# smart-plug.net
KiCad netlist of a schematic drawn in Altium Designer
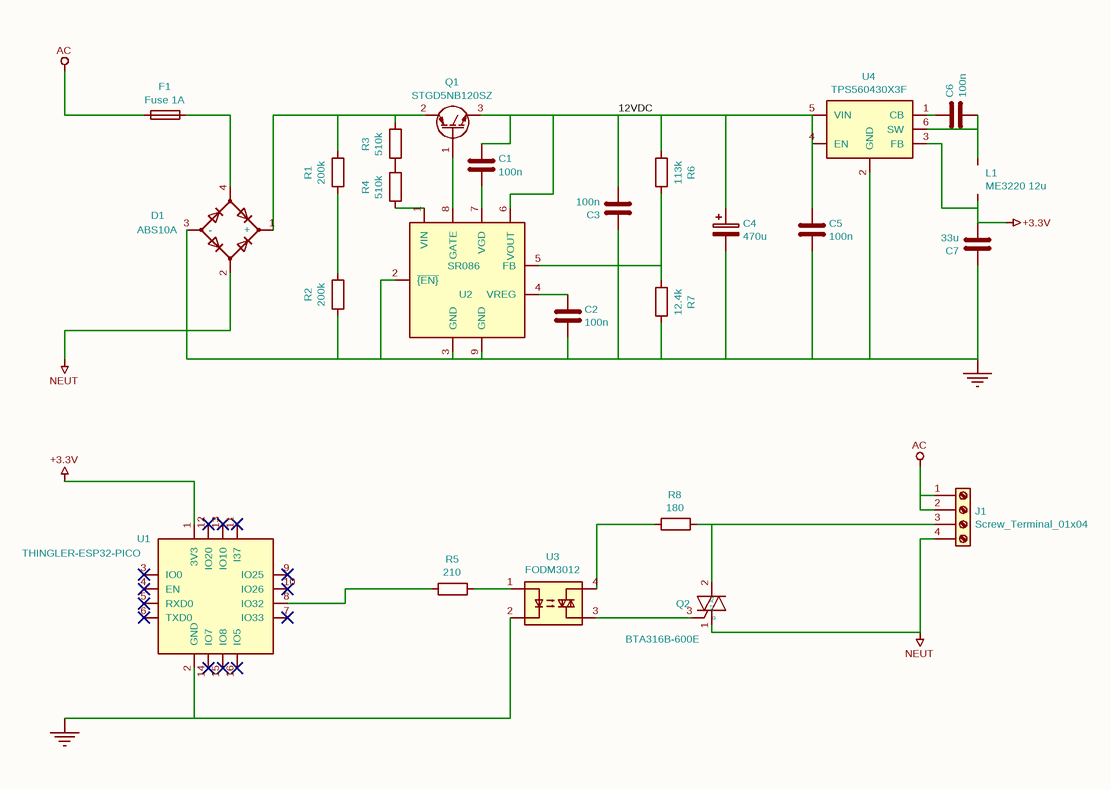
[diagram p0: smart-plug.SchDoc]

(export (version "E")
  (design (tool "Eeschema 10.0.6"))
  (components
    (comp (ref "C1") (value "100n") (libsource (lib "Device") (part "C")))
    (comp (ref "C2") (value "100n") (libsource (lib "Device") (part "C")))
    (comp (ref "C3") (value "100n") (libsource (lib "Device") (part "C")))
    (comp (ref "C4") (value "470u") (libsource (lib "Device") (part "C_Polarized")))
    (comp (ref "C5") (value "100n") (libsource (lib "Device") (part "C")))
    (comp (ref "C6") (value "100n") (libsource (lib "Device") (part "C")))
    (comp (ref "C7") (value "33u") (libsource (lib "Device") (part "C")))
    (comp (ref "D1") (value "ABS10A") (libsource (lib "Device") (part "D_Bridge_+A-A")))
    (comp (ref "F1") (value "Fuse 1A") (libsource (lib "Device") (part "Fuse")))
    (comp (ref "J1")
      (value "Screw_Terminal_01x04")
      (libsource (lib "Connector") (part "Screw_Terminal_01x04"))
    )
    (comp (ref "L1") (value "ME3220 12u") (libsource (lib "Device") (part "L")))
    (comp (ref "Q1") (value "STGD5NB120SZ") (libsource (lib "Device") (part "Q_NIGBT_GCE")))
    (comp (ref "Q2") (value "BTA316B-600E") (libsource (lib "Triac_Thyristor") (part "BT138-600")))
    (comp (ref "R1") (value "200k") (libsource (lib "Device") (part "R")))
    (comp (ref "R2") (value "200k") (libsource (lib "Device") (part "R")))
    (comp (ref "R3") (value "510k") (libsource (lib "Device") (part "R")))
    (comp (ref "R4") (value "510k") (libsource (lib "Device") (part "R")))
    (comp (ref "R5") (value "210") (libsource (lib "") (part "R_1")))
    (comp (ref "R6") (value "113k") (libsource (lib "") (part "R_2")))
    (comp (ref "R7") (value "12.4k") (libsource (lib "") (part "R_2")))
    (comp (ref "R8") (value "180") (libsource (lib "") (part "R_1")))
    (comp (ref "U1")
      (value "THINGLER-ESP32-PICO")
      (libsource (lib "smart-plug") (part "THINGLER-ESP32-PICO"))
    )
    (comp (ref "U2") (value "SR086") (libsource (lib "smart-plug") (part "SR086")))
    (comp (ref "U3") (value "FODM3012") (libsource (lib "Relay_SolidState") (part "FODM3012")))
    (comp (ref "U4") (value "TPS560430X3F") (libsource (lib "smart-plug") (part "TPS560430")))
  )
  (nets
    (net (code "1") (name "+3.3V") (class "Default")
      (node (ref "C7") (pin "2") (pinfunction "2_2") (pintype "passive"))
      (node (ref "L1") (pin "2") (pinfunction "2_2") (pintype "passive"))
      (node (ref "U1") (pin "1") (pinfunction "3V3_1") (pintype "passive"))
      (node (ref "U4") (pin "3") (pinfunction "FB_3") (pintype "passive"))
    )
    (net (code "2") (name "/12VDC") (class "Default")
      (node (ref "C1") (pin "1") (pinfunction "1_1") (pintype "passive"))
      (node (ref "C3") (pin "2") (pinfunction "2_2") (pintype "passive"))
      (node (ref "C4") (pin "1") (pinfunction "1_1") (pintype "passive"))
      (node (ref "C5") (pin "1") (pinfunction "1_1") (pintype "passive"))
      (node (ref "Q1") (pin "3") (pinfunction "E_3") (pintype "passive"))
      (node (ref "R6") (pin "2") (pinfunction "2_2") (pintype "passive"))
      (node (ref "U2") (pin "6") (pinfunction "VOUT_6") (pintype "passive"))
      (node (ref "U4") (pin "4") (pinfunction "EN_4") (pintype "passive"))
      (node (ref "U4") (pin "5") (pinfunction "VIN_5") (pintype "passive"))
    )
    (net (code "3") (name "AC") (class "Default")
      (node (ref "F1") (pin "2") (pinfunction "2_2") (pintype "passive"))
      (node (ref "J1") (pin "1") (pinfunction "Pin_1_1") (pintype "passive"))
      (node (ref "J1") (pin "2") (pinfunction "Pin_2_2") (pintype "passive"))
    )
    (net (code "4") (name "Earth") (class "Default")
      (node (ref "C2") (pin "2") (pinfunction "2_2") (pintype "passive"))
      (node (ref "C3") (pin "1") (pinfunction "1_1") (pintype "passive"))
      (node (ref "C4") (pin "2") (pinfunction "2_2") (pintype "passive"))
      (node (ref "C5") (pin "2") (pinfunction "2_2") (pintype "passive"))
      (node (ref "C7") (pin "1") (pinfunction "1_1") (pintype "passive"))
      (node (ref "D1") (pin "3") (pinfunction "-_3") (pintype "passive"))
      (node (ref "R2") (pin "2") (pinfunction "2_2") (pintype "passive"))
      (node (ref "R7") (pin "1") (pinfunction "1_1") (pintype "passive"))
      (node (ref "U1") (pin "2") (pinfunction "GND_2") (pintype "passive"))
      (node (ref "U2") (pin "2") (pinfunction "~{{EN}}_2") (pintype "passive"))
      (node (ref "U2") (pin "3") (pinfunction "GND_3") (pintype "passive"))
      (node (ref "U2") (pin "9") (pinfunction "GND_9") (pintype "passive"))
      (node (ref "U3") (pin "2") (pinfunction "2_2") (pintype "passive"))
      (node (ref "U4") (pin "2") (pinfunction "GND_2") (pintype "passive"))
    )
    (net (code "5") (name "NEUT") (class "Default")
      (node (ref "D1") (pin "2") (pinfunction "2_2") (pintype "passive"))
      (node (ref "J1") (pin "4") (pinfunction "Pin_4_4") (pintype "passive"))
      (node (ref "Q2") (pin "1") (pinfunction "A1_1") (pintype "passive"))
    )
    (net (code "6") (name "Net-(D1-+)") (class "Default")
      (node (ref "D1") (pin "1") (pinfunction "+_1") (pintype "passive"))
      (node (ref "Q1") (pin "2") (pinfunction "C_2") (pintype "passive"))
      (node (ref "R1") (pin "1") (pinfunction "1_1") (pintype "passive"))
      (node (ref "R3") (pin "1") (pinfunction "1_1") (pintype "passive"))
    )
    (net (code "7") (name "Net-(D1-Pad4)") (class "Default")
      (node (ref "D1") (pin "4") (pinfunction "4_4") (pintype "passive"))
      (node (ref "F1") (pin "1") (pinfunction "1_1") (pintype "passive"))
    )
    (net (code "8") (name "Net-(J1-Pin_3)") (class "Default")
      (node (ref "J1") (pin "3") (pinfunction "Pin_3_3") (pintype "passive"))
      (node (ref "Q2") (pin "2") (pinfunction "A2_2") (pintype "passive"))
      (node (ref "R8") (pin "1") (pinfunction "1_1") (pintype "passive"))
    )
    (net (code "9") (name "Net-(Q1-G)") (class "Default")
      (node (ref "Q1") (pin "1") (pinfunction "G_1") (pintype "passive"))
      (node (ref "U2") (pin "8") (pinfunction "GATE_8") (pintype "passive"))
    )
    (net (code "10") (name "Net-(Q2-G)") (class "Default")
      (node (ref "Q2") (pin "3") (pinfunction "G_3") (pintype "passive"))
      (node (ref "U3") (pin "3") (pinfunction "3_3") (pintype "passive"))
    )
    (net (code "11") (name "Net-(R1-Pad2)") (class "Default")
      (node (ref "R1") (pin "2") (pinfunction "2_2") (pintype "passive"))
      (node (ref "R2") (pin "1") (pinfunction "1_1") (pintype "passive"))
    )
    (net (code "12") (name "Net-(R3-Pad2)") (class "Default")
      (node (ref "R3") (pin "2") (pinfunction "2_2") (pintype "passive"))
      (node (ref "R4") (pin "1") (pinfunction "1_1") (pintype "passive"))
    )
    (net (code "13") (name "Net-(R5-Pad1)") (class "Default")
      (node (ref "R5") (pin "1") (pinfunction "1_1") (pintype "passive"))
      (node (ref "U3") (pin "1") (pinfunction "1_1") (pintype "passive"))
    )
    (net (code "14") (name "Net-(R8-Pad2)") (class "Default")
      (node (ref "R8") (pin "2") (pinfunction "2_2") (pintype "passive"))
      (node (ref "U3") (pin "4") (pinfunction "4_4") (pintype "passive"))
    )
    (net (code "15") (name "Net-(U1-IO32)") (class "Default")
      (node (ref "R5") (pin "2") (pinfunction "2_2") (pintype "passive"))
      (node (ref "U1") (pin "8") (pinfunction "IO32_8") (pintype "passive"))
    )
    (net (code "16") (name "Net-(U2-FB)") (class "Default")
      (node (ref "R6") (pin "1") (pinfunction "1_1") (pintype "passive"))
      (node (ref "R7") (pin "2") (pinfunction "2_2") (pintype "passive"))
      (node (ref "U2") (pin "5") (pinfunction "FB_5") (pintype "passive"))
    )
    (net (code "17") (name "Net-(U2-VGD)") (class "Default")
      (node (ref "C1") (pin "2") (pinfunction "2_2") (pintype "passive"))
      (node (ref "U2") (pin "7") (pinfunction "VGD_7") (pintype "passive"))
    )
    (net (code "18") (name "Net-(U2-VIN)") (class "Default")
      (node (ref "R4") (pin "2") (pinfunction "2_2") (pintype "passive"))
      (node (ref "U2") (pin "1") (pinfunction "VIN_1") (pintype "passive"))
    )
    (net (code "19") (name "Net-(U2-VREG)") (class "Default")
      (node (ref "C2") (pin "1") (pinfunction "1_1") (pintype "passive"))
      (node (ref "U2") (pin "4") (pinfunction "VREG_4") (pintype "passive"))
    )
    (net (code "20") (name "Net-(U4-CB)") (class "Default")
      (node (ref "C6") (pin "1") (pinfunction "1_1") (pintype "passive"))
      (node (ref "U4") (pin "1") (pinfunction "CB_1") (pintype "passive"))
    )
    (net (code "21") (name "Net-(U4-SW)") (class "Default")
      (node (ref "C6") (pin "2") (pinfunction "2_2") (pintype "passive"))
      (node (ref "L1") (pin "1") (pinfunction "1_1") (pintype "passive"))
      (node (ref "U4") (pin "6") (pinfunction "SW_6") (pintype "passive"))
    )
    (net (code "22") (name "unconnected-(U1-EN-Pad4)") (class "Default")
      (node (ref "U1") (pin "4") (pinfunction "EN_4") (pintype "passive+no_connect"))
    )
    (net (code "23") (name "unconnected-(U1-I37-Pad11)") (class "Default")
      (node (ref "U1") (pin "11") (pinfunction "I37_11") (pintype "passive+no_connect"))
    )
    (net (code "24") (name "unconnected-(U1-IO0-Pad3)") (class "Default")
      (node (ref "U1") (pin "3") (pinfunction "IO0_3") (pintype "passive+no_connect"))
    )
    (net (code "25") (name "unconnected-(U1-IO5-Pad16)") (class "Default")
      (node (ref "U1") (pin "16") (pinfunction "IO5_16") (pintype "passive+no_connect"))
    )
    (net (code "26") (name "unconnected-(U1-IO7-Pad14)") (class "Default")
      (node (ref "U1") (pin "14") (pinfunction "IO7_14") (pintype "passive+no_connect"))
    )
    (net (code "27") (name "unconnected-(U1-IO8-Pad15)") (class "Default")
      (node (ref "U1") (pin "15") (pinfunction "IO8_15") (pintype "passive+no_connect"))
    )
    (net (code "28") (name "unconnected-(U1-IO10-Pad13)") (class "Default")
      (node (ref "U1") (pin "13") (pinfunction "IO10_13") (pintype "passive+no_connect"))
    )
    (net (code "29") (name "unconnected-(U1-IO20-Pad12)") (class "Default")
      (node (ref "U1") (pin "12") (pinfunction "IO20_12") (pintype "passive+no_connect"))
    )
    (net (code "30") (name "unconnected-(U1-IO25-Pad9)") (class "Default")
      (node (ref "U1") (pin "9") (pinfunction "IO25_9") (pintype "passive+no_connect"))
    )
    (net (code "31") (name "unconnected-(U1-IO26-Pad10)") (class "Default")
      (node (ref "U1") (pin "10") (pinfunction "IO26_10") (pintype "passive+no_connect"))
    )
    (net (code "32") (name "unconnected-(U1-IO33-Pad7)") (class "Default")
      (node (ref "U1") (pin "7") (pinfunction "IO33_7") (pintype "passive+no_connect"))
    )
    (net (code "33") (name "unconnected-(U1-RXD0-Pad5)") (class "Default")
      (node (ref "U1") (pin "5") (pinfunction "RXD0_5") (pintype "passive+no_connect"))
    )
    (net (code "34") (name "unconnected-(U1-TXD0-Pad6)") (class "Default")
      (node (ref "U1") (pin "6") (pinfunction "TXD0_6") (pintype "passive+no_connect"))
    )
  )
)
